# FSR.net
KiCad netlist of a schematic drawn in Altium Designer
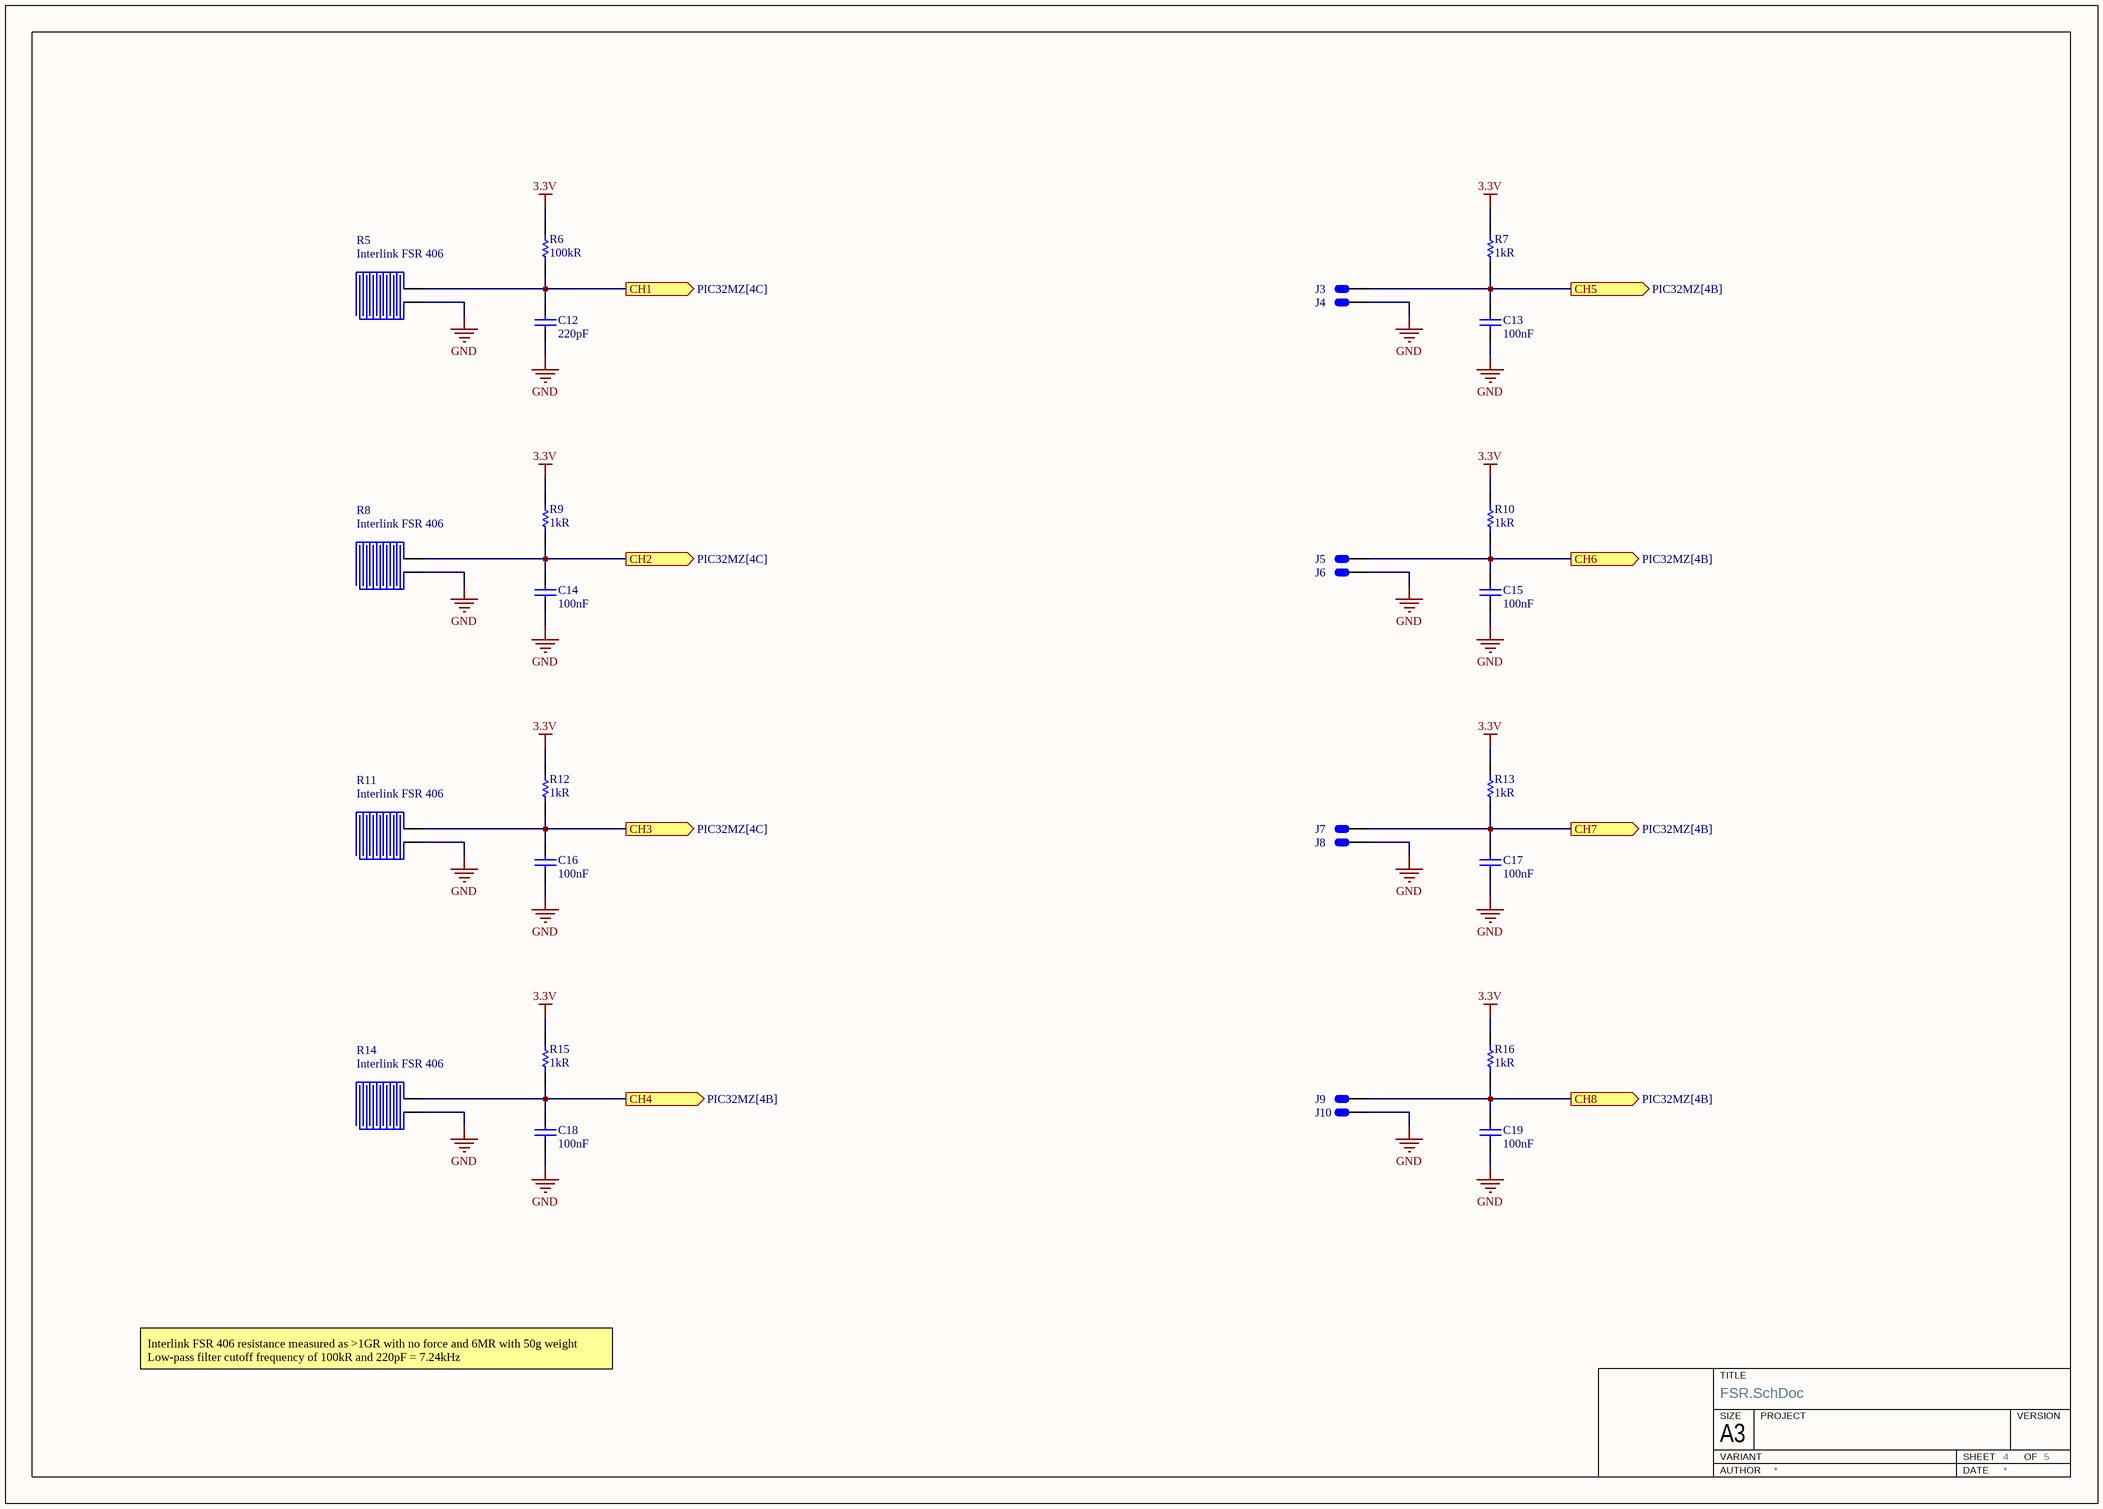
[diagram p0: FSR.SchDoc]

(export (version "E")
  (design (tool "Eeschema 10.0.6"))
  (components
    (comp (ref "C12")
      (value "220pF")
      (footprint "Capacitor 0402")
      (libsource (lib "x-io") (part "Capacitor"))
    )
    (comp (ref "C13")
      (value "100nF")
      (footprint "Capacitor 0402")
      (libsource (lib "x-io") (part "Capacitor"))
    )
    (comp (ref "C14")
      (value "100nF")
      (footprint "Capacitor 0402")
      (libsource (lib "x-io") (part "Capacitor"))
    )
    (comp (ref "C15")
      (value "100nF")
      (footprint "Capacitor 0402")
      (libsource (lib "x-io") (part "Capacitor"))
    )
    (comp (ref "C16")
      (value "100nF")
      (footprint "Capacitor 0402")
      (libsource (lib "x-io") (part "Capacitor"))
    )
    (comp (ref "C17")
      (value "100nF")
      (footprint "Capacitor 0402")
      (libsource (lib "x-io") (part "Capacitor"))
    )
    (comp (ref "C18")
      (value "100nF")
      (footprint "Capacitor 0402")
      (libsource (lib "x-io") (part "Capacitor"))
    )
    (comp (ref "C19")
      (value "100nF")
      (footprint "Capacitor 0402")
      (libsource (lib "x-io") (part "Capacitor"))
    )
    (comp (ref "J3")
      (value "Wire Solder Pad")
      (footprint "Wire Solder Pad 3x1.5mm")
      (libsource (lib "x-io") (part "Wire Solder Pad"))
    )
    (comp (ref "J4")
      (value "Wire Solder Pad")
      (footprint "Wire Solder Pad 3x1.5mm")
      (libsource (lib "x-io") (part "Wire Solder Pad"))
    )
    (comp (ref "J5")
      (value "Wire Solder Pad")
      (footprint "Wire Solder Pad 3x1.5mm")
      (libsource (lib "x-io") (part "Wire Solder Pad"))
    )
    (comp (ref "J6")
      (value "Wire Solder Pad")
      (footprint "Wire Solder Pad 3x1.5mm")
      (libsource (lib "x-io") (part "Wire Solder Pad"))
    )
    (comp (ref "J7")
      (value "Wire Solder Pad")
      (footprint "Wire Solder Pad 3x1.5mm")
      (libsource (lib "x-io") (part "Wire Solder Pad"))
    )
    (comp (ref "J8")
      (value "Wire Solder Pad")
      (footprint "Wire Solder Pad 3x1.5mm")
      (libsource (lib "x-io") (part "Wire Solder Pad"))
    )
    (comp (ref "J9")
      (value "Wire Solder Pad")
      (footprint "Wire Solder Pad 3x1.5mm")
      (libsource (lib "x-io") (part "Wire Solder Pad"))
    )
    (comp (ref "J10")
      (value "Wire Solder Pad")
      (footprint "Wire Solder Pad 3x1.5mm")
      (libsource (lib "x-io") (part "Wire Solder Pad"))
    )
    (comp (ref "R5")
      (value "Interlink FSR 406")
      (footprint "Interlink FSR 406")
      (libsource (lib "x-io") (part "Interlink FSR 406"))
    )
    (comp (ref "R6") (value "100kR") (footprint "Resistor 0402") (libsource (lib "x-io") (part "Resistor")))
    (comp (ref "R7") (value "1kR") (footprint "Resistor 0402") (libsource (lib "x-io") (part "Resistor")))
    (comp (ref "R8")
      (value "Interlink FSR 406")
      (footprint "Interlink FSR 406")
      (libsource (lib "x-io") (part "Interlink FSR 406"))
    )
    (comp (ref "R9") (value "1kR") (footprint "Resistor 0402") (libsource (lib "x-io") (part "Resistor")))
    (comp (ref "R10") (value "1kR") (footprint "Resistor 0402") (libsource (lib "x-io") (part "Resistor")))
    (comp (ref "R11")
      (value "Interlink FSR 406")
      (footprint "Interlink FSR 406")
      (libsource (lib "x-io") (part "Interlink FSR 406"))
    )
    (comp (ref "R12") (value "1kR") (footprint "Resistor 0402") (libsource (lib "x-io") (part "Resistor")))
    (comp (ref "R13") (value "1kR") (footprint "Resistor 0402") (libsource (lib "x-io") (part "Resistor")))
    (comp (ref "R14")
      (value "Interlink FSR 406")
      (footprint "Interlink FSR 406")
      (libsource (lib "x-io") (part "Interlink FSR 406"))
    )
    (comp (ref "R15") (value "1kR") (footprint "Resistor 0402") (libsource (lib "x-io") (part "Resistor")))
    (comp (ref "R16") (value "1kR") (footprint "Resistor 0402") (libsource (lib "x-io") (part "Resistor")))
  )
  (nets
    (net (code "1") (name "/CH1") (class "Default")
      (node (ref "C12") (pin "2") (pinfunction "2_2") (pintype "passive"))
      (node (ref "R5") (pin "1") (pinfunction "1_1") (pintype "passive"))
      (node (ref "R6") (pin "1") (pinfunction "1_1") (pintype "passive"))
    )
    (net (code "2") (name "/CH2") (class "Default")
      (node (ref "C14") (pin "2") (pinfunction "2_2") (pintype "passive"))
      (node (ref "R8") (pin "1") (pinfunction "1_1") (pintype "passive"))
      (node (ref "R9") (pin "1") (pinfunction "1_1") (pintype "passive"))
    )
    (net (code "3") (name "/CH3") (class "Default")
      (node (ref "C16") (pin "2") (pinfunction "2_2") (pintype "passive"))
      (node (ref "R11") (pin "1") (pinfunction "1_1") (pintype "passive"))
      (node (ref "R12") (pin "1") (pinfunction "1_1") (pintype "passive"))
    )
    (net (code "4") (name "/CH4") (class "Default")
      (node (ref "C18") (pin "2") (pinfunction "2_2") (pintype "passive"))
      (node (ref "R14") (pin "1") (pinfunction "1_1") (pintype "passive"))
      (node (ref "R15") (pin "1") (pinfunction "1_1") (pintype "passive"))
    )
    (net (code "5") (name "/CH5") (class "Default")
      (node (ref "C13") (pin "2") (pinfunction "2_2") (pintype "passive"))
      (node (ref "J3") (pin "1") (pinfunction "1_1") (pintype "passive"))
      (node (ref "R7") (pin "1") (pinfunction "1_1") (pintype "passive"))
    )
    (net (code "6") (name "/CH6") (class "Default")
      (node (ref "C15") (pin "2") (pinfunction "2_2") (pintype "passive"))
      (node (ref "J5") (pin "1") (pinfunction "1_1") (pintype "passive"))
      (node (ref "R10") (pin "1") (pinfunction "1_1") (pintype "passive"))
    )
    (net (code "7") (name "/CH7") (class "Default")
      (node (ref "C17") (pin "2") (pinfunction "2_2") (pintype "passive"))
      (node (ref "J7") (pin "1") (pinfunction "1_1") (pintype "passive"))
      (node (ref "R13") (pin "1") (pinfunction "1_1") (pintype "passive"))
    )
    (net (code "8") (name "/CH8") (class "Default")
      (node (ref "C19") (pin "2") (pinfunction "2_2") (pintype "passive"))
      (node (ref "J9") (pin "1") (pinfunction "1_1") (pintype "passive"))
      (node (ref "R16") (pin "1") (pinfunction "1_1") (pintype "passive"))
    )
    (net (code "9") (name "3.3V") (class "Default")
      (node (ref "R10") (pin "2") (pinfunction "2_2") (pintype "passive"))
      (node (ref "R12") (pin "2") (pinfunction "2_2") (pintype "passive"))
      (node (ref "R13") (pin "2") (pinfunction "2_2") (pintype "passive"))
      (node (ref "R15") (pin "2") (pinfunction "2_2") (pintype "passive"))
      (node (ref "R16") (pin "2") (pinfunction "2_2") (pintype "passive"))
      (node (ref "R6") (pin "2") (pinfunction "2_2") (pintype "passive"))
      (node (ref "R7") (pin "2") (pinfunction "2_2") (pintype "passive"))
      (node (ref "R9") (pin "2") (pinfunction "2_2") (pintype "passive"))
    )
    (net (code "10") (name "GND") (class "Default")
      (node (ref "C12") (pin "1") (pinfunction "1_1") (pintype "passive"))
      (node (ref "C13") (pin "1") (pinfunction "1_1") (pintype "passive"))
      (node (ref "C14") (pin "1") (pinfunction "1_1") (pintype "passive"))
      (node (ref "C15") (pin "1") (pinfunction "1_1") (pintype "passive"))
      (node (ref "C16") (pin "1") (pinfunction "1_1") (pintype "passive"))
      (node (ref "C17") (pin "1") (pinfunction "1_1") (pintype "passive"))
      (node (ref "C18") (pin "1") (pinfunction "1_1") (pintype "passive"))
      (node (ref "C19") (pin "1") (pinfunction "1_1") (pintype "passive"))
      (node (ref "J10") (pin "1") (pinfunction "1_1") (pintype "passive"))
      (node (ref "J4") (pin "1") (pinfunction "1_1") (pintype "passive"))
      (node (ref "J6") (pin "1") (pinfunction "1_1") (pintype "passive"))
      (node (ref "J8") (pin "1") (pinfunction "1_1") (pintype "passive"))
      (node (ref "R11") (pin "2") (pinfunction "2_2") (pintype "passive"))
      (node (ref "R14") (pin "2") (pinfunction "2_2") (pintype "passive"))
      (node (ref "R5") (pin "2") (pinfunction "2_2") (pintype "passive"))
      (node (ref "R8") (pin "2") (pinfunction "2_2") (pintype "passive"))
    )
  )
)
